# mcp2221.net
KiCad netlist of a schematic drawn in EAGLE
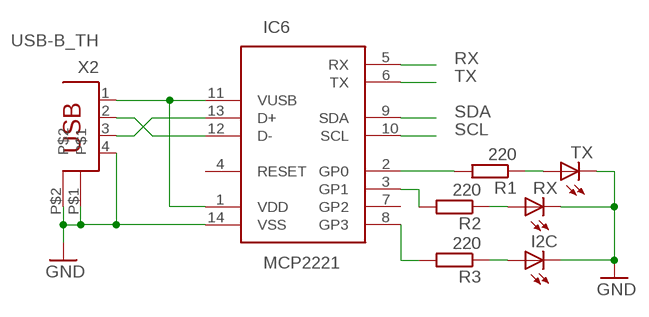
[diagram p0: schematic, sheet 1]

(export (version "E")
  (design (tool "Eeschema 10.0.6"))
  (components
    (comp (ref "I2C")
      (value "LED5MM")
      (footprint "eagle-import:LED5MM")
      (libsource (lib "eagle-import") (part "LED5MM"))
    )
    (comp (ref "IC6")
      (value "MCP2221")
      (footprint "eagle-import:DIL14")
      (libsource (lib "eagle-import") (part "MCP2221"))
    )
    (comp (ref "R1")
      (value "220")
      (footprint "eagle-import:0207_10")
      (libsource (lib "eagle-import") (part "R-EU_0207/10"))
    )
    (comp (ref "R2")
      (value "220")
      (footprint "eagle-import:0207_10")
      (libsource (lib "eagle-import") (part "R-EU_0207/10"))
    )
    (comp (ref "R3")
      (value "220")
      (footprint "eagle-import:0207_10")
      (libsource (lib "eagle-import") (part "R-EU_0207/10"))
    )
    (comp (ref "RX")
      (value "LED5MM")
      (footprint "eagle-import:LED5MM")
      (libsource (lib "eagle-import") (part "LED5MM"))
    )
    (comp (ref "TX")
      (value "LED5MM")
      (footprint "eagle-import:LED5MM")
      (libsource (lib "eagle-import") (part "LED5MM"))
    )
    (comp (ref "X2")
      (value "USB-B_TH")
      (footprint "eagle-import:PN61729")
      (libsource (lib "eagle-import") (part "PN61729"))
    )
  )
  (nets
    (net (code "1") (name "/RX") (class "Default")
      (node (ref "IC6") (pin "5") (pinfunction "RX_5") (pintype "bidirectional"))
    )
    (net (code "2") (name "/SCL") (class "Default")
      (node (ref "IC6") (pin "10") (pinfunction "SCL_10") (pintype "bidirectional"))
    )
    (net (code "3") (name "/SDA") (class "Default")
      (node (ref "IC6") (pin "9") (pinfunction "SDA_9") (pintype "bidirectional"))
    )
    (net (code "4") (name "/TX") (class "Default")
      (node (ref "IC6") (pin "6") (pinfunction "TX_6") (pintype "bidirectional"))
    )
    (net (code "5") (name "GND") (class "Default")
      (node (ref "I2C") (pin "K") (pinfunction "C_K") (pintype "passive"))
      (node (ref "IC6") (pin "14") (pinfunction "VSS_14") (pintype "bidirectional"))
      (node (ref "RX") (pin "K") (pinfunction "C_K") (pintype "passive"))
      (node (ref "TX") (pin "K") (pinfunction "C_K") (pintype "passive"))
      (node (ref "X2") (pin "4") (pinfunction "4_4") (pintype "bidirectional"))
      (node (ref "X2") (pin "P$1") (pinfunction "P$1_P$1") (pintype "bidirectional"))
      (node (ref "X2") (pin "P$2") (pinfunction "P$2_P$2") (pintype "bidirectional"))
    )
    (net (code "6") (name "Net-(I2C-PadA)") (class "Default")
      (node (ref "I2C") (pin "A") (pinfunction "A_A") (pintype "passive"))
      (node (ref "R3") (pin "1") (pinfunction "1_1") (pintype "passive"))
    )
    (net (code "7") (name "Net-(IC6-D+)") (class "Default")
      (node (ref "IC6") (pin "13") (pinfunction "D+_13") (pintype "bidirectional"))
      (node (ref "X2") (pin "3") (pinfunction "3_3") (pintype "bidirectional"))
    )
    (net (code "8") (name "Net-(IC6-D-)") (class "Default")
      (node (ref "IC6") (pin "12") (pinfunction "D-_12") (pintype "bidirectional"))
      (node (ref "X2") (pin "2") (pinfunction "2_2") (pintype "bidirectional"))
    )
    (net (code "9") (name "Net-(IC6-GP0)") (class "Default")
      (node (ref "IC6") (pin "2") (pinfunction "GP0_2") (pintype "bidirectional"))
      (node (ref "R1") (pin "2") (pinfunction "2_2") (pintype "passive"))
    )
    (net (code "10") (name "Net-(IC6-GP1)") (class "Default")
      (node (ref "IC6") (pin "3") (pinfunction "GP1_3") (pintype "bidirectional"))
      (node (ref "R2") (pin "2") (pinfunction "2_2") (pintype "passive"))
    )
    (net (code "11") (name "Net-(IC6-GP3)") (class "Default")
      (node (ref "IC6") (pin "8") (pinfunction "GP3_8") (pintype "bidirectional"))
      (node (ref "R3") (pin "2") (pinfunction "2_2") (pintype "passive"))
    )
    (net (code "12") (name "Net-(IC6-VDD)") (class "Default")
      (node (ref "IC6") (pin "1") (pinfunction "VDD_1") (pintype "bidirectional"))
      (node (ref "IC6") (pin "11") (pinfunction "VUSB_11") (pintype "bidirectional"))
      (node (ref "X2") (pin "1") (pinfunction "1_1") (pintype "bidirectional"))
    )
    (net (code "13") (name "Net-(R1-Pad1)") (class "Default")
      (node (ref "R1") (pin "1") (pinfunction "1_1") (pintype "passive"))
      (node (ref "TX") (pin "A") (pinfunction "A_A") (pintype "passive"))
    )
    (net (code "14") (name "Net-(R2-Pad1)") (class "Default")
      (node (ref "R2") (pin "1") (pinfunction "1_1") (pintype "passive"))
      (node (ref "RX") (pin "A") (pinfunction "A_A") (pintype "passive"))
    )
    (net (code "15") (name "unconnected-(IC6-GP2-Pad7)") (class "Default")
      (node (ref "IC6") (pin "7") (pinfunction "GP2_7") (pintype "bidirectional"))
    )
    (net (code "16") (name "unconnected-(IC6-RESET-Pad4)") (class "Default")
      (node (ref "IC6") (pin "4") (pinfunction "RESET_4") (pintype "bidirectional"))
    )
  )
)
